# Temperature.net
KiCad netlist of a schematic drawn in Altium Designer
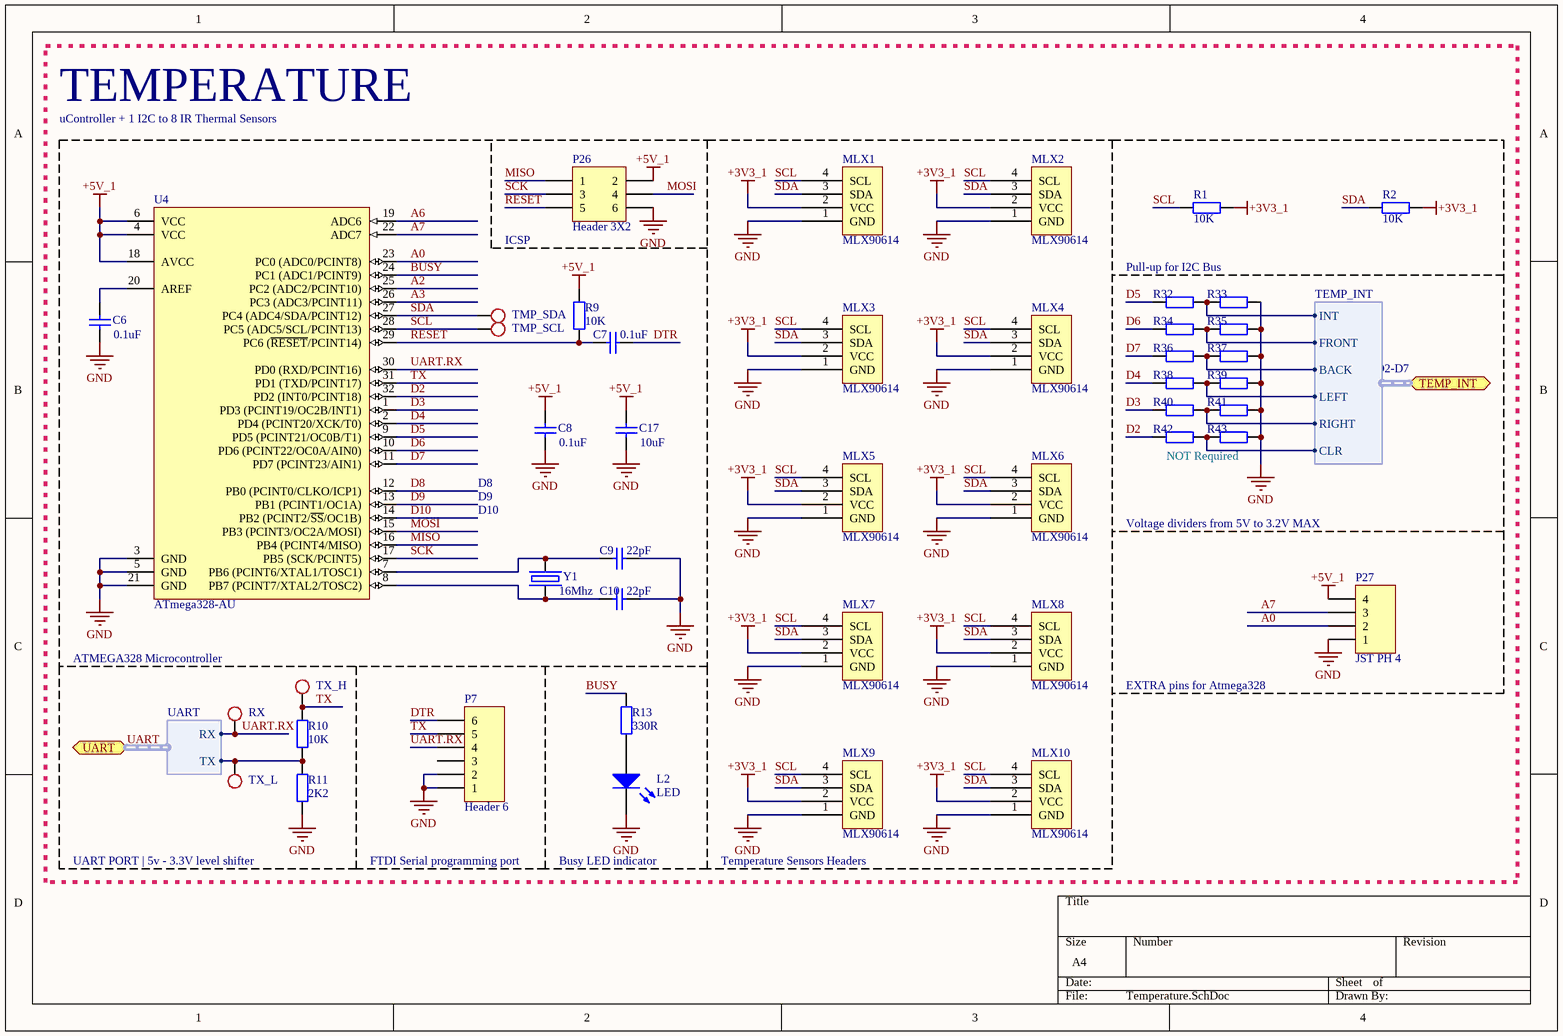
[diagram p0: Temperature.SchDoc]

(export (version "E")
  (design (tool "Eeschema 10.0.6"))
  (components
    (comp (ref "C6")
      (value "0.1uF")
      (footprint "C0805")
      (description "Capacitor (Semiconductor SIM Model)")
      (fields (field (name "PUBLISHER") "Altium Limited"))
      (libsource (lib "Miscellaneous Devices") (part "Cap Semi"))
    )
    (comp (ref "C7")
      (value "0.1uF")
      (footprint "C0805")
      (description "Capacitor (Semiconductor SIM Model)")
      (fields (field (name "PUBLISHER") "Altium Limited"))
      (libsource (lib "Miscellaneous Devices") (part "Cap Semi"))
    )
    (comp (ref "C8")
      (value "0.1uF")
      (footprint "C0805")
      (description "Capacitor (Semiconductor SIM Model)")
      (fields (field (name "PUBLISHER") "Altium Limited"))
      (libsource (lib "Miscellaneous Devices") (part "Cap Semi"))
    )
    (comp (ref "C9")
      (value "22pF")
      (footprint "C0805")
      (description "Capacitor (Semiconductor SIM Model)")
      (fields (field (name "PUBLISHER") "Altium Limited"))
      (libsource (lib "Miscellaneous Devices") (part "Cap Semi"))
    )
    (comp (ref "C10")
      (value "22pF")
      (footprint "C0805")
      (description "Capacitor (Semiconductor SIM Model)")
      (fields (field (name "PUBLISHER") "Altium Limited"))
      (libsource (lib "Miscellaneous Devices") (part "Cap Semi"))
    )
    (comp (ref "C17")
      (value "10uF")
      (footprint "C1206")
      (description "Capacitor (Semiconductor SIM Model)")
      (fields (field (name "PUBLISHER") "Altium Limited"))
      (libsource (lib "Miscellaneous Devices") (part "Cap Semi"))
    )
    (comp (ref "L2") (value "LED") (footprint "LED0805") (libsource (lib "CustomLibrary") (part "LED")))
    (comp (ref "MLX1")
      (value "MLX90614")
      (footprint "MLX-BREAKOUT")
      (libsource (lib "CustomLibrary") (part "MLX-BREAKOUT"))
    )
    (comp (ref "MLX2")
      (value "MLX90614")
      (footprint "MLX-BREAKOUT")
      (libsource (lib "CustomLibrary") (part "MLX-BREAKOUT"))
    )
    (comp (ref "MLX3")
      (value "MLX90614")
      (footprint "MLX-BREAKOUT")
      (libsource (lib "CustomLibrary") (part "MLX-BREAKOUT"))
    )
    (comp (ref "MLX4")
      (value "MLX90614")
      (footprint "MLX-BREAKOUT")
      (libsource (lib "CustomLibrary") (part "MLX-BREAKOUT"))
    )
    (comp (ref "MLX5")
      (value "MLX90614")
      (footprint "MLX-BREAKOUT")
      (libsource (lib "CustomLibrary") (part "MLX-BREAKOUT"))
    )
    (comp (ref "MLX6")
      (value "MLX90614")
      (footprint "MLX-BREAKOUT")
      (libsource (lib "CustomLibrary") (part "MLX-BREAKOUT"))
    )
    (comp (ref "MLX7")
      (value "MLX90614")
      (footprint "MLX-BREAKOUT")
      (libsource (lib "CustomLibrary") (part "MLX-BREAKOUT"))
    )
    (comp (ref "MLX8")
      (value "MLX90614")
      (footprint "MLX-BREAKOUT")
      (libsource (lib "CustomLibrary") (part "MLX-BREAKOUT"))
    )
    (comp (ref "MLX9")
      (value "MLX90614")
      (footprint "MLX-BREAKOUT")
      (libsource (lib "CustomLibrary") (part "MLX-BREAKOUT"))
    )
    (comp (ref "MLX10")
      (value "MLX90614")
      (footprint "MLX-BREAKOUT")
      (libsource (lib "CustomLibrary") (part "MLX-BREAKOUT"))
    )
    (comp (ref "P7")
      (value "Header 6")
      (footprint "HDR1X6")
      (description "Header, 6-Pin")
      (fields (field (name "PUBLISHER") "Altium Limited"))
      (libsource (lib "Miscellaneous Connectors") (part "Header 6"))
    )
    (comp (ref "P26")
      (value "Header 3X2")
      (footprint "HDR2X3")
      (description "Header, 3-Pin, Dual row")
      (fields (field (name "PUBLISHER") "Altium Limited"))
      (libsource (lib "Miscellaneous Connectors") (part "Header 3X2"))
    )
    (comp (ref "P27")
      (value "JST PH 4")
      (footprint "B4B-PH-K")
      (libsource (lib "CustomLibrary") (part "JST PH 4"))
    )
    (comp (ref "R1") (value "10K") (footprint "RES1206") (libsource (lib "CustomLibrary") (part "RES")))
    (comp (ref "R2") (value "10K") (footprint "RES1206") (libsource (lib "CustomLibrary") (part "RES")))
    (comp (ref "R9") (value "10K") (footprint "RES1206") (libsource (lib "") (part "RES_1")))
    (comp (ref "R10") (value "10K") (footprint "RES1206") (libsource (lib "") (part "RES_2")))
    (comp (ref "R11") (value "2K2") (footprint "RES1206") (libsource (lib "") (part "RES_2")))
    (comp (ref "R13") (value "330R") (footprint "RES1206") (libsource (lib "") (part "RES_2")))
    (comp (ref "R32") (value "10K") (footprint "RES1206") (libsource (lib "CustomLibrary") (part "RES")))
    (comp (ref "R33") (value "2K2") (footprint "RES1206") (libsource (lib "CustomLibrary") (part "RES")))
    (comp (ref "R34") (value "10K") (footprint "RES1206") (libsource (lib "CustomLibrary") (part "RES")))
    (comp (ref "R35") (value "2K2") (footprint "RES1206") (libsource (lib "CustomLibrary") (part "RES")))
    (comp (ref "R36") (value "10K") (footprint "RES1206") (libsource (lib "CustomLibrary") (part "RES")))
    (comp (ref "R37") (value "2K2") (footprint "RES1206") (libsource (lib "CustomLibrary") (part "RES")))
    (comp (ref "R38") (value "10K") (footprint "RES1206") (libsource (lib "CustomLibrary") (part "RES")))
    (comp (ref "R39") (value "2K2") (footprint "RES1206") (libsource (lib "CustomLibrary") (part "RES")))
    (comp (ref "R40") (value "10K") (footprint "RES1206") (libsource (lib "CustomLibrary") (part "RES")))
    (comp (ref "R41") (value "2K2") (footprint "RES1206") (libsource (lib "CustomLibrary") (part "RES")))
    (comp (ref "R42") (value "10K") (footprint "RES1206") (libsource (lib "CustomLibrary") (part "RES")))
    (comp (ref "R43") (value "2K2") (footprint "RES1206") (libsource (lib "CustomLibrary") (part "RES")))
    (comp (ref "RX")
      (value "Test Point")
      (footprint "TP1")
      (description "Test Point for Osciloscope measurements")
      (libsource (lib "CustomLibrary") (part "Test Point"))
    )
    (comp (ref "TMP_SCL")
      (value "Test Point")
      (footprint "TP1")
      (description "Test Point for Osciloscope measurements")
      (libsource (lib "CustomLibrary") (part "Test Point"))
    )
    (comp (ref "TMP_SDA")
      (value "Test Point")
      (footprint "TP1")
      (description "Test Point for Osciloscope measurements")
      (libsource (lib "CustomLibrary") (part "Test Point"))
    )
    (comp (ref "TX_H")
      (value "Test Point")
      (footprint "TP1")
      (description "Test Point for Osciloscope measurements")
      (libsource (lib "CustomLibrary") (part "Test Point"))
    )
    (comp (ref "TX_L")
      (value "Test Point")
      (footprint "TP1")
      (description "Test Point for Osciloscope measurements")
      (libsource (lib "CustomLibrary") (part "Test Point"))
    )
    (comp (ref "U4")
      (value "ATmega328-AU")
      (footprint "32A_N")
      (fields (field (name "PUBLISHER") "Altium Limited"))
      (libsource (lib "Atmel Microcontroller 8-Bit megaAVR") (part "ATmega328-AU"))
    )
    (comp (ref "Y1")
      (value "16Mhz")
      (footprint "OSC-2-PIN-TH")
      (description "2 pin oscilator")
      (libsource (lib "CustomLibrary") (part "OSC-2-PIN"))
    )
  )
  (nets
    (net (code "3") (name "+3V3_1") (class "Default")
      (node (ref "MLX1") (pin "2") (pinfunction "VCC_2") (pintype "passive"))
      (node (ref "MLX10") (pin "2") (pinfunction "VCC_2") (pintype "passive"))
      (node (ref "MLX2") (pin "2") (pinfunction "VCC_2") (pintype "passive"))
      (node (ref "MLX3") (pin "2") (pinfunction "VCC_2") (pintype "passive"))
      (node (ref "MLX4") (pin "2") (pinfunction "VCC_2") (pintype "passive"))
      (node (ref "MLX5") (pin "2") (pinfunction "VCC_2") (pintype "passive"))
      (node (ref "MLX6") (pin "2") (pinfunction "VCC_2") (pintype "passive"))
      (node (ref "MLX7") (pin "2") (pinfunction "VCC_2") (pintype "passive"))
      (node (ref "MLX8") (pin "2") (pinfunction "VCC_2") (pintype "passive"))
      (node (ref "MLX9") (pin "2") (pinfunction "VCC_2") (pintype "passive"))
      (node (ref "R1") (pin "2") (pinfunction "2_2") (pintype "passive"))
      (node (ref "R2") (pin "2") (pinfunction "2_2") (pintype "passive"))
    )
    (net (code "4") (name "+5V_1") (class "Default")
      (node (ref "C17") (pin "2") (pinfunction "2_2") (pintype "passive"))
      (node (ref "C8") (pin "2") (pinfunction "2_2") (pintype "passive"))
      (node (ref "P26") (pin "2") (pinfunction "2_2") (pintype "passive"))
      (node (ref "P27") (pin "4") (pinfunction "4_4") (pintype "passive"))
      (node (ref "R9") (pin "1") (pinfunction "1_1") (pintype "passive"))
      (node (ref "U4") (pin "18") (pinfunction "AVCC_18") (pintype "power_in"))
      (node (ref "U4") (pin "4") (pinfunction "VCC_4") (pintype "power_in"))
      (node (ref "U4") (pin "6") (pinfunction "VCC_6") (pintype "power_in"))
    )
    (net (code "5") (name "/A0") (class "Default")
      (node (ref "P27") (pin "2") (pinfunction "2_2") (pintype "passive"))
      (node (ref "U4") (pin "23") (pinfunction "PC0_(ADC0/PCINT8)_23") (pintype "bidirectional"))
    )
    (net (code "6") (name "/A2") (class "Default")
      (node (ref "U4") (pin "25") (pinfunction "PC2_(ADC2/PCINT10)_25") (pintype "bidirectional"))
    )
    (net (code "7") (name "/A3") (class "Default")
      (node (ref "U4") (pin "26") (pinfunction "PC3_(ADC3/PCINT11)_26") (pintype "bidirectional"))
    )
    (net (code "8") (name "/A6") (class "Default")
      (node (ref "U4") (pin "19") (pinfunction "ADC6_19") (pintype "input"))
    )
    (net (code "9") (name "/A7") (class "Default")
      (node (ref "P27") (pin "3") (pinfunction "3_3") (pintype "passive"))
      (node (ref "U4") (pin "22") (pinfunction "ADC7_22") (pintype "input"))
    )
    (net (code "10") (name "/BUSY") (class "Default")
      (node (ref "R13") (pin "2") (pinfunction "2_2") (pintype "passive"))
      (node (ref "U4") (pin "24") (pinfunction "PC1_(ADC1/PCINT9)_24") (pintype "bidirectional"))
    )
    (net (code "11") (name "/D2") (class "Default")
      (node (ref "R42") (pin "1") (pinfunction "1_1") (pintype "passive"))
      (node (ref "U4") (pin "32") (pinfunction "PD2_(INT0/PCINT18)_32") (pintype "bidirectional"))
    )
    (net (code "12") (name "/D3") (class "Default")
      (node (ref "R40") (pin "1") (pinfunction "1_1") (pintype "passive"))
      (node (ref "U4") (pin "1") (pinfunction "PD3_(PCINT19/OC2B/INT1)_1") (pintype "bidirectional"))
    )
    (net (code "13") (name "/D4") (class "Default")
      (node (ref "R38") (pin "1") (pinfunction "1_1") (pintype "passive"))
      (node (ref "U4") (pin "2") (pinfunction "PD4_(PCINT20/XCK/T0)_2") (pintype "bidirectional"))
    )
    (net (code "14") (name "/D5") (class "Default")
      (node (ref "R32") (pin "1") (pinfunction "1_1") (pintype "passive"))
      (node (ref "U4") (pin "9") (pinfunction "PD5_(PCINT21/OC0B/T1)_9") (pintype "bidirectional"))
    )
    (net (code "15") (name "/D6") (class "Default")
      (node (ref "R34") (pin "1") (pinfunction "1_1") (pintype "passive"))
      (node (ref "U4") (pin "10") (pinfunction "PD6_(PCINT22/OC0A/AIN0)_10") (pintype "bidirectional"))
    )
    (net (code "16") (name "/D7") (class "Default")
      (node (ref "R36") (pin "1") (pinfunction "1_1") (pintype "passive"))
      (node (ref "U4") (pin "11") (pinfunction "PD7_(PCINT23/AIN1)_11") (pintype "bidirectional"))
    )
    (net (code "17") (name "/D8") (class "Default")
      (node (ref "U4") (pin "12") (pinfunction "PB0_(PCINT0/CLKO/ICP1)_12") (pintype "bidirectional"))
    )
    (net (code "18") (name "/D9") (class "Default")
      (node (ref "U4") (pin "13") (pinfunction "PB1_(PCINT1/OC1A)_13") (pintype "bidirectional"))
    )
    (net (code "19") (name "/D10") (class "Default")
      (node (ref "U4") (pin "14") (pinfunction "PB2_(PCINT2/~{SS}/OC1B)_14") (pintype "bidirectional"))
    )
    (net (code "20") (name "/DTR") (class "Default")
      (node (ref "C7") (pin "2") (pinfunction "2_2") (pintype "passive"))
      (node (ref "P7") (pin "6") (pinfunction "6_6") (pintype "passive"))
    )
    (net (code "21") (name "/MISO") (class "Default")
      (node (ref "P26") (pin "1") (pinfunction "1_1") (pintype "passive"))
      (node (ref "U4") (pin "16") (pinfunction "PB4_(PCINT4/MISO)_16") (pintype "bidirectional"))
    )
    (net (code "22") (name "/MOSI") (class "Default")
      (node (ref "P26") (pin "4") (pinfunction "4_4") (pintype "passive"))
      (node (ref "U4") (pin "15") (pinfunction "PB3_(PCINT3/OC2A/MOSI)_15") (pintype "bidirectional"))
    )
    (net (code "23") (name "/RESET") (class "Default")
      (node (ref "C7") (pin "1") (pinfunction "1_1") (pintype "passive"))
      (node (ref "P26") (pin "5") (pinfunction "5_5") (pintype "passive"))
      (node (ref "R9") (pin "2") (pinfunction "2_2") (pintype "passive"))
      (node (ref "U4") (pin "29") (pinfunction "PC6_(~{RESET}/PCINT14)_29") (pintype "bidirectional"))
    )
    (net (code "24") (name "/SCK") (class "Default")
      (node (ref "P26") (pin "3") (pinfunction "3_3") (pintype "passive"))
      (node (ref "U4") (pin "17") (pinfunction "PB5_(SCK/PCINT5)_17") (pintype "bidirectional"))
    )
    (net (code "25") (name "/SCL") (class "Default")
      (node (ref "MLX1") (pin "4") (pinfunction "SCL_4") (pintype "passive"))
      (node (ref "MLX10") (pin "4") (pinfunction "SCL_4") (pintype "passive"))
      (node (ref "MLX2") (pin "4") (pinfunction "SCL_4") (pintype "passive"))
      (node (ref "MLX3") (pin "4") (pinfunction "SCL_4") (pintype "passive"))
      (node (ref "MLX4") (pin "4") (pinfunction "SCL_4") (pintype "passive"))
      (node (ref "MLX5") (pin "4") (pinfunction "SCL_4") (pintype "passive"))
      (node (ref "MLX6") (pin "4") (pinfunction "SCL_4") (pintype "passive"))
      (node (ref "MLX7") (pin "4") (pinfunction "SCL_4") (pintype "passive"))
      (node (ref "MLX8") (pin "4") (pinfunction "SCL_4") (pintype "passive"))
      (node (ref "MLX9") (pin "4") (pinfunction "SCL_4") (pintype "passive"))
      (node (ref "R1") (pin "1") (pinfunction "1_1") (pintype "passive"))
      (node (ref "TMP_SCL") (pin "1") (pinfunction "1_1") (pintype "passive"))
      (node (ref "U4") (pin "28") (pinfunction "PC5_(ADC5/SCL/PCINT13)_28") (pintype "bidirectional"))
    )
    (net (code "26") (name "/SDA") (class "Default")
      (node (ref "MLX1") (pin "3") (pinfunction "SDA_3") (pintype "passive"))
      (node (ref "MLX10") (pin "3") (pinfunction "SDA_3") (pintype "passive"))
      (node (ref "MLX2") (pin "3") (pinfunction "SDA_3") (pintype "passive"))
      (node (ref "MLX3") (pin "3") (pinfunction "SDA_3") (pintype "passive"))
      (node (ref "MLX4") (pin "3") (pinfunction "SDA_3") (pintype "passive"))
      (node (ref "MLX5") (pin "3") (pinfunction "SDA_3") (pintype "passive"))
      (node (ref "MLX6") (pin "3") (pinfunction "SDA_3") (pintype "passive"))
      (node (ref "MLX7") (pin "3") (pinfunction "SDA_3") (pintype "passive"))
      (node (ref "MLX8") (pin "3") (pinfunction "SDA_3") (pintype "passive"))
      (node (ref "MLX9") (pin "3") (pinfunction "SDA_3") (pintype "passive"))
      (node (ref "R2") (pin "1") (pinfunction "1_1") (pintype "passive"))
      (node (ref "TMP_SDA") (pin "1") (pinfunction "1_1") (pintype "passive"))
      (node (ref "U4") (pin "27") (pinfunction "PC4_(ADC4/SDA/PCINT12)_27") (pintype "bidirectional"))
    )
    (net (code "27") (name "/TX") (class "Default")
      (node (ref "P7") (pin "5") (pinfunction "5_5") (pintype "passive"))
      (node (ref "R10") (pin "2") (pinfunction "2_2") (pintype "passive"))
      (node (ref "TX_H") (pin "1") (pinfunction "1_1") (pintype "passive"))
      (node (ref "U4") (pin "31") (pinfunction "PD1_(TXD/PCINT17)_31") (pintype "bidirectional"))
    )
    (net (code "28") (name "/UART.RX") (class "Default")
      (node (ref "P7") (pin "4") (pinfunction "4_4") (pintype "passive"))
      (node (ref "RX") (pin "1") (pinfunction "1_1") (pintype "passive"))
      (node (ref "U4") (pin "30") (pinfunction "PD0_(RXD/PCINT16)_30") (pintype "bidirectional"))
    )
    (net (code "31") (name "GND") (class "Default")
      (node (ref "C10") (pin "2") (pinfunction "2_2") (pintype "passive"))
      (node (ref "C17") (pin "1") (pinfunction "1_1") (pintype "passive"))
      (node (ref "C6") (pin "1") (pinfunction "1_1") (pintype "passive"))
      (node (ref "C8") (pin "1") (pinfunction "1_1") (pintype "passive"))
      (node (ref "C9") (pin "2") (pinfunction "2_2") (pintype "passive"))
      (node (ref "L2") (pin "2") (pinfunction "K_2") (pintype "passive"))
      (node (ref "MLX1") (pin "1") (pinfunction "GND_1") (pintype "passive"))
      (node (ref "MLX10") (pin "1") (pinfunction "GND_1") (pintype "passive"))
      (node (ref "MLX2") (pin "1") (pinfunction "GND_1") (pintype "passive"))
      (node (ref "MLX3") (pin "1") (pinfunction "GND_1") (pintype "passive"))
      (node (ref "MLX4") (pin "1") (pinfunction "GND_1") (pintype "passive"))
      (node (ref "MLX5") (pin "1") (pinfunction "GND_1") (pintype "passive"))
      (node (ref "MLX6") (pin "1") (pinfunction "GND_1") (pintype "passive"))
      (node (ref "MLX7") (pin "1") (pinfunction "GND_1") (pintype "passive"))
      (node (ref "MLX8") (pin "1") (pinfunction "GND_1") (pintype "passive"))
      (node (ref "MLX9") (pin "1") (pinfunction "GND_1") (pintype "passive"))
      (node (ref "P26") (pin "6") (pinfunction "6_6") (pintype "passive"))
      (node (ref "P27") (pin "1") (pinfunction "1_1") (pintype "passive"))
      (node (ref "P7") (pin "1") (pinfunction "1_1") (pintype "passive"))
      (node (ref "P7") (pin "2") (pinfunction "2_2") (pintype "passive"))
      (node (ref "R11") (pin "1") (pinfunction "1_1") (pintype "passive"))
      (node (ref "R33") (pin "2") (pinfunction "2_2") (pintype "passive"))
      (node (ref "R35") (pin "2") (pinfunction "2_2") (pintype "passive"))
      (node (ref "R37") (pin "2") (pinfunction "2_2") (pintype "passive"))
      (node (ref "R39") (pin "2") (pinfunction "2_2") (pintype "passive"))
      (node (ref "R41") (pin "2") (pinfunction "2_2") (pintype "passive"))
      (node (ref "R43") (pin "2") (pinfunction "2_2") (pintype "passive"))
      (node (ref "U4") (pin "21") (pinfunction "GND_21") (pintype "power_in"))
      (node (ref "U4") (pin "3") (pinfunction "GND_3") (pintype "power_in"))
      (node (ref "U4") (pin "5") (pinfunction "GND_5") (pintype "power_in"))
    )
    (net (code "32") (name "Net-(L2-A)") (class "Default")
      (node (ref "L2") (pin "1") (pinfunction "A_1") (pintype "passive"))
      (node (ref "R13") (pin "1") (pinfunction "1_1") (pintype "passive"))
    )
    (net (code "33") (name "Net-(R10-Pad1)") (class "Default")
      (node (ref "R10") (pin "1") (pinfunction "1_1") (pintype "passive"))
      (node (ref "R11") (pin "2") (pinfunction "2_2") (pintype "passive"))
      (node (ref "TX_L") (pin "1") (pinfunction "1_1") (pintype "passive"))
    )
    (net (code "34") (name "Net-(R32-Pad2)") (class "Default")
      (node (ref "R32") (pin "2") (pinfunction "2_2") (pintype "passive"))
      (node (ref "R33") (pin "1") (pinfunction "1_1") (pintype "passive"))
    )
    (net (code "35") (name "Net-(R34-Pad2)") (class "Default")
      (node (ref "R34") (pin "2") (pinfunction "2_2") (pintype "passive"))
      (node (ref "R35") (pin "1") (pinfunction "1_1") (pintype "passive"))
    )
    (net (code "36") (name "Net-(R36-Pad2)") (class "Default")
      (node (ref "R36") (pin "2") (pinfunction "2_2") (pintype "passive"))
      (node (ref "R37") (pin "1") (pinfunction "1_1") (pintype "passive"))
    )
    (net (code "37") (name "Net-(R38-Pad2)") (class "Default")
      (node (ref "R38") (pin "2") (pinfunction "2_2") (pintype "passive"))
      (node (ref "R39") (pin "1") (pinfunction "1_1") (pintype "passive"))
    )
    (net (code "38") (name "Net-(R40-Pad2)") (class "Default")
      (node (ref "R40") (pin "2") (pinfunction "2_2") (pintype "passive"))
      (node (ref "R41") (pin "1") (pinfunction "1_1") (pintype "passive"))
    )
    (net (code "39") (name "Net-(R42-Pad2)") (class "Default")
      (node (ref "R42") (pin "2") (pinfunction "2_2") (pintype "passive"))
      (node (ref "R43") (pin "1") (pinfunction "1_1") (pintype "passive"))
    )
    (net (code "40") (name "Net-(U4-AREF)") (class "Default")
      (node (ref "C6") (pin "2") (pinfunction "2_2") (pintype "passive"))
      (node (ref "U4") (pin "20") (pinfunction "AREF_20") (pintype "passive"))
    )
    (net (code "41") (name "Net-(U4-PB6_(PCINT6{slash}XTAL1{slash}TOSC1))") (class "Default")
      (node (ref "C9") (pin "1") (pinfunction "1_1") (pintype "passive"))
      (node (ref "U4") (pin "7") (pinfunction "PB6_(PCINT6/XTAL1/TOSC1)_7") (pintype "bidirectional"))
      (node (ref "Y1") (pin "1") (pinfunction "1_1") (pintype "passive"))
    )
    (net (code "42") (name "Net-(U4-PB7_(PCINT7{slash}XTAL2{slash}TOSC2))") (class "Default")
      (node (ref "C10") (pin "1") (pinfunction "1_1") (pintype "passive"))
      (node (ref "U4") (pin "8") (pinfunction "PB7_(PCINT7/XTAL2/TOSC2)_8") (pintype "bidirectional"))
      (node (ref "Y1") (pin "2") (pinfunction "2_2") (pintype "passive"))
    )
    (net (code "43") (name "unconnected-(P7-Pad3)") (class "Default")
      (node (ref "P7") (pin "3") (pinfunction "3_3") (pintype "passive"))
    )
  )
)
